# ai_breakout_tinyspi.net
KiCad netlist of a schematic drawn in EAGLE
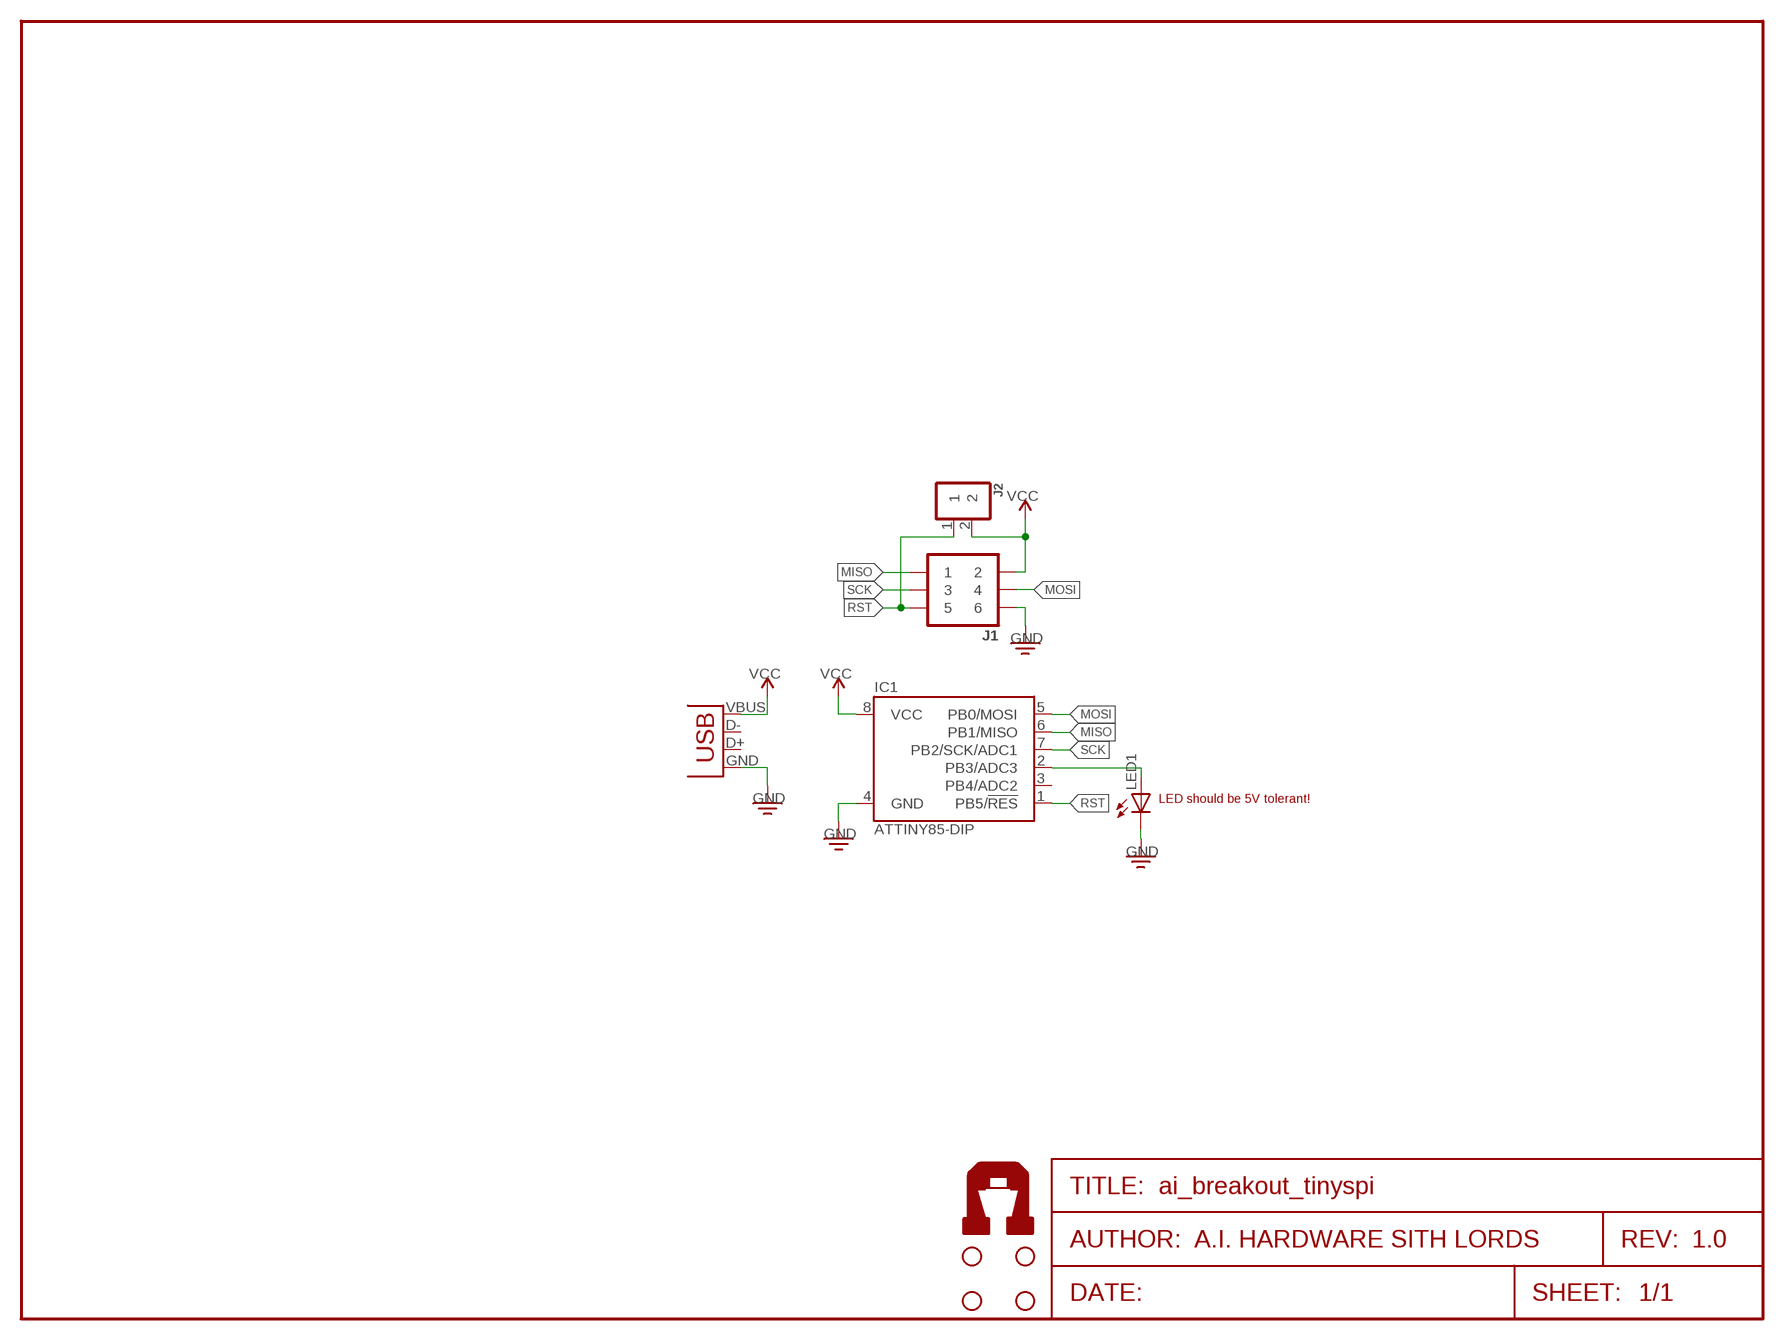
[diagram p0: schematic, sheet 1]

(export (version "E")
  (design (tool "Eeschema 10.0.6"))
  (components
    (comp (ref "IC1")
      (value "ATTINY85-DIP")
      (footprint "eagle-import:DIL08")
      (libsource (lib "eagle-import") (part "ATTINY85-DIP"))
    )
    (comp (ref "J1")
      (value "2X03")
      (footprint "eagle-import:2X03")
      (libsource (lib "eagle-import") (part "2X03"))
    )
    (comp (ref "J2")
      (value "1X02NOFIRST")
      (footprint "eagle-import:1X02-NOFIRST")
      (libsource (lib "eagle-import") (part "1X02NOFIRST"))
    )
    (comp (ref "LED1")
      (value "LED5MM")
      (footprint "eagle-import:LED-5MM")
      (libsource (lib "eagle-import") (part "LED5MM"))
    )
    (comp (ref "STANDOFF1")
      (value "STAND-OFF")
      (footprint "eagle-import:STAND-OFF")
      (libsource (lib "eagle-import") (part "STAND-OFF"))
    )
    (comp (ref "STANDOFF2")
      (value "STAND-OFF")
      (footprint "eagle-import:STAND-OFF")
      (libsource (lib "eagle-import") (part "STAND-OFF"))
    )
    (comp (ref "STANDOFF3")
      (value "STAND-OFF")
      (footprint "eagle-import:STAND-OFF")
      (libsource (lib "eagle-import") (part "STAND-OFF"))
    )
    (comp (ref "STANDOFF4")
      (value "STAND-OFF")
      (footprint "eagle-import:STAND-OFF")
      (libsource (lib "eagle-import") (part "STAND-OFF"))
    )
    (comp (ref "U$1")
      (value "AI-LOGOXS")
      (footprint "eagle-import:AI-LOGO-XS")
      (libsource (lib "eagle-import") (part "AI-LOGOXS"))
    )
    (comp (ref "USB1")
      (value "USBMICROB-TH")
      (footprint "eagle-import:USB-MICROB-TH")
      (libsource (lib "eagle-import") (part "USBMICROB-TH"))
    )
  )
  (nets
    (net (code "1") (name "GND") (class "Default")
      (node (ref "IC1") (pin "4") (pinfunction "GND_4") (pintype "bidirectional"))
      (node (ref "J1") (pin "6") (pinfunction "6_6") (pintype "bidirectional"))
      (node (ref "LED1") (pin "C") (pinfunction "C_C") (pintype "passive"))
      (node (ref "USB1") (pin "GND") (pinfunction "GND_GND") (pintype "bidirectional"))
    )
    (net (code "2") (name "MISO") (class "Default")
      (node (ref "IC1") (pin "6") (pinfunction "PB1/MISO_6") (pintype "bidirectional"))
      (node (ref "J1") (pin "1") (pinfunction "1_1") (pintype "bidirectional"))
    )
    (net (code "3") (name "MOSI") (class "Default")
      (node (ref "IC1") (pin "5") (pinfunction "PB0/MOSI_5") (pintype "bidirectional"))
      (node (ref "J1") (pin "4") (pinfunction "4_4") (pintype "bidirectional"))
    )
    (net (code "4") (name "Net-(IC1-PB3{slash}ADC3)") (class "Default")
      (node (ref "IC1") (pin "2") (pinfunction "PB3/ADC3_2") (pintype "bidirectional"))
      (node (ref "LED1") (pin "A") (pinfunction "A_A") (pintype "passive"))
    )
    (net (code "5") (name "RST") (class "Default")
      (node (ref "IC1") (pin "1") (pinfunction "PB5/~{RES}_1") (pintype "bidirectional"))
      (node (ref "J1") (pin "5") (pinfunction "5_5") (pintype "bidirectional"))
      (node (ref "J2") (pin "1") (pinfunction "1_1") (pintype "bidirectional"))
    )
    (net (code "6") (name "SCK") (class "Default")
      (node (ref "IC1") (pin "7") (pinfunction "PB2/SCK/ADC1_7") (pintype "bidirectional"))
      (node (ref "J1") (pin "3") (pinfunction "3_3") (pintype "bidirectional"))
    )
    (net (code "7") (name "VCC") (class "Default")
      (node (ref "IC1") (pin "8") (pinfunction "VCC_8") (pintype "bidirectional"))
      (node (ref "J1") (pin "2") (pinfunction "2_2") (pintype "bidirectional"))
      (node (ref "J2") (pin "2") (pinfunction "2_2") (pintype "bidirectional"))
      (node (ref "USB1") (pin "VBUS") (pinfunction "VBUS_VBUS") (pintype "bidirectional"))
    )
    (net (code "8") (name "unconnected-(IC1-PB4{slash}ADC2-Pad3)") (class "Default")
      (node (ref "IC1") (pin "3") (pinfunction "PB4/ADC2_3") (pintype "bidirectional"))
    )
    (net (code "9") (name "unconnected-(USB1-PadD+)") (class "Default")
      (node (ref "USB1") (pin "D+") (pinfunction "D+_D+") (pintype "bidirectional"))
    )
    (net (code "10") (name "unconnected-(USB1-PadD-)") (class "Default")
      (node (ref "USB1") (pin "D-") (pinfunction "D-_D-") (pintype "bidirectional"))
    )
  )
)
